# embedded-gw.net
KiCad netlist of a schematic drawn in EAGLE
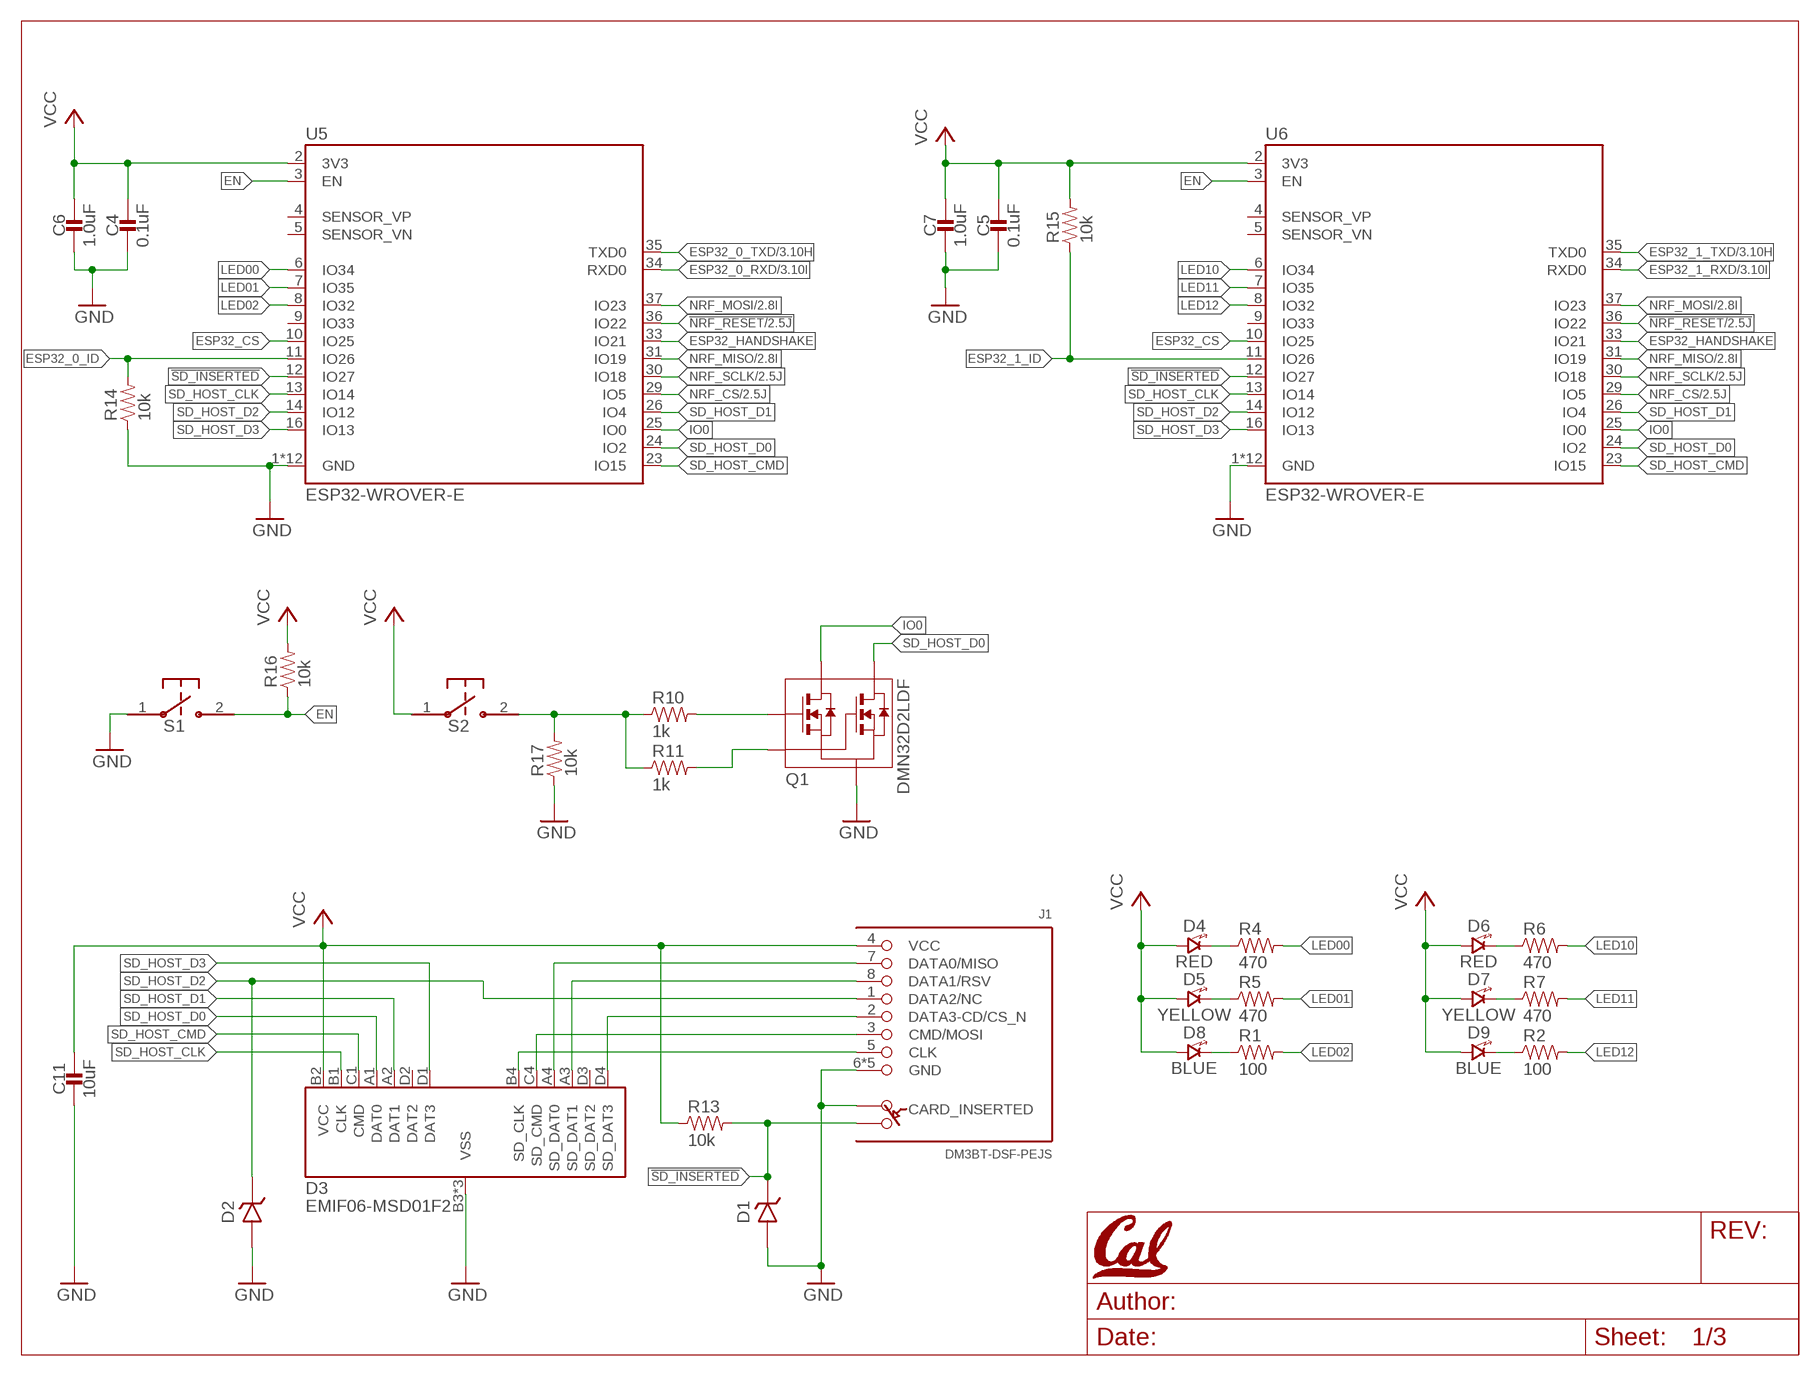
[diagram p0: schematic, sheet 1]
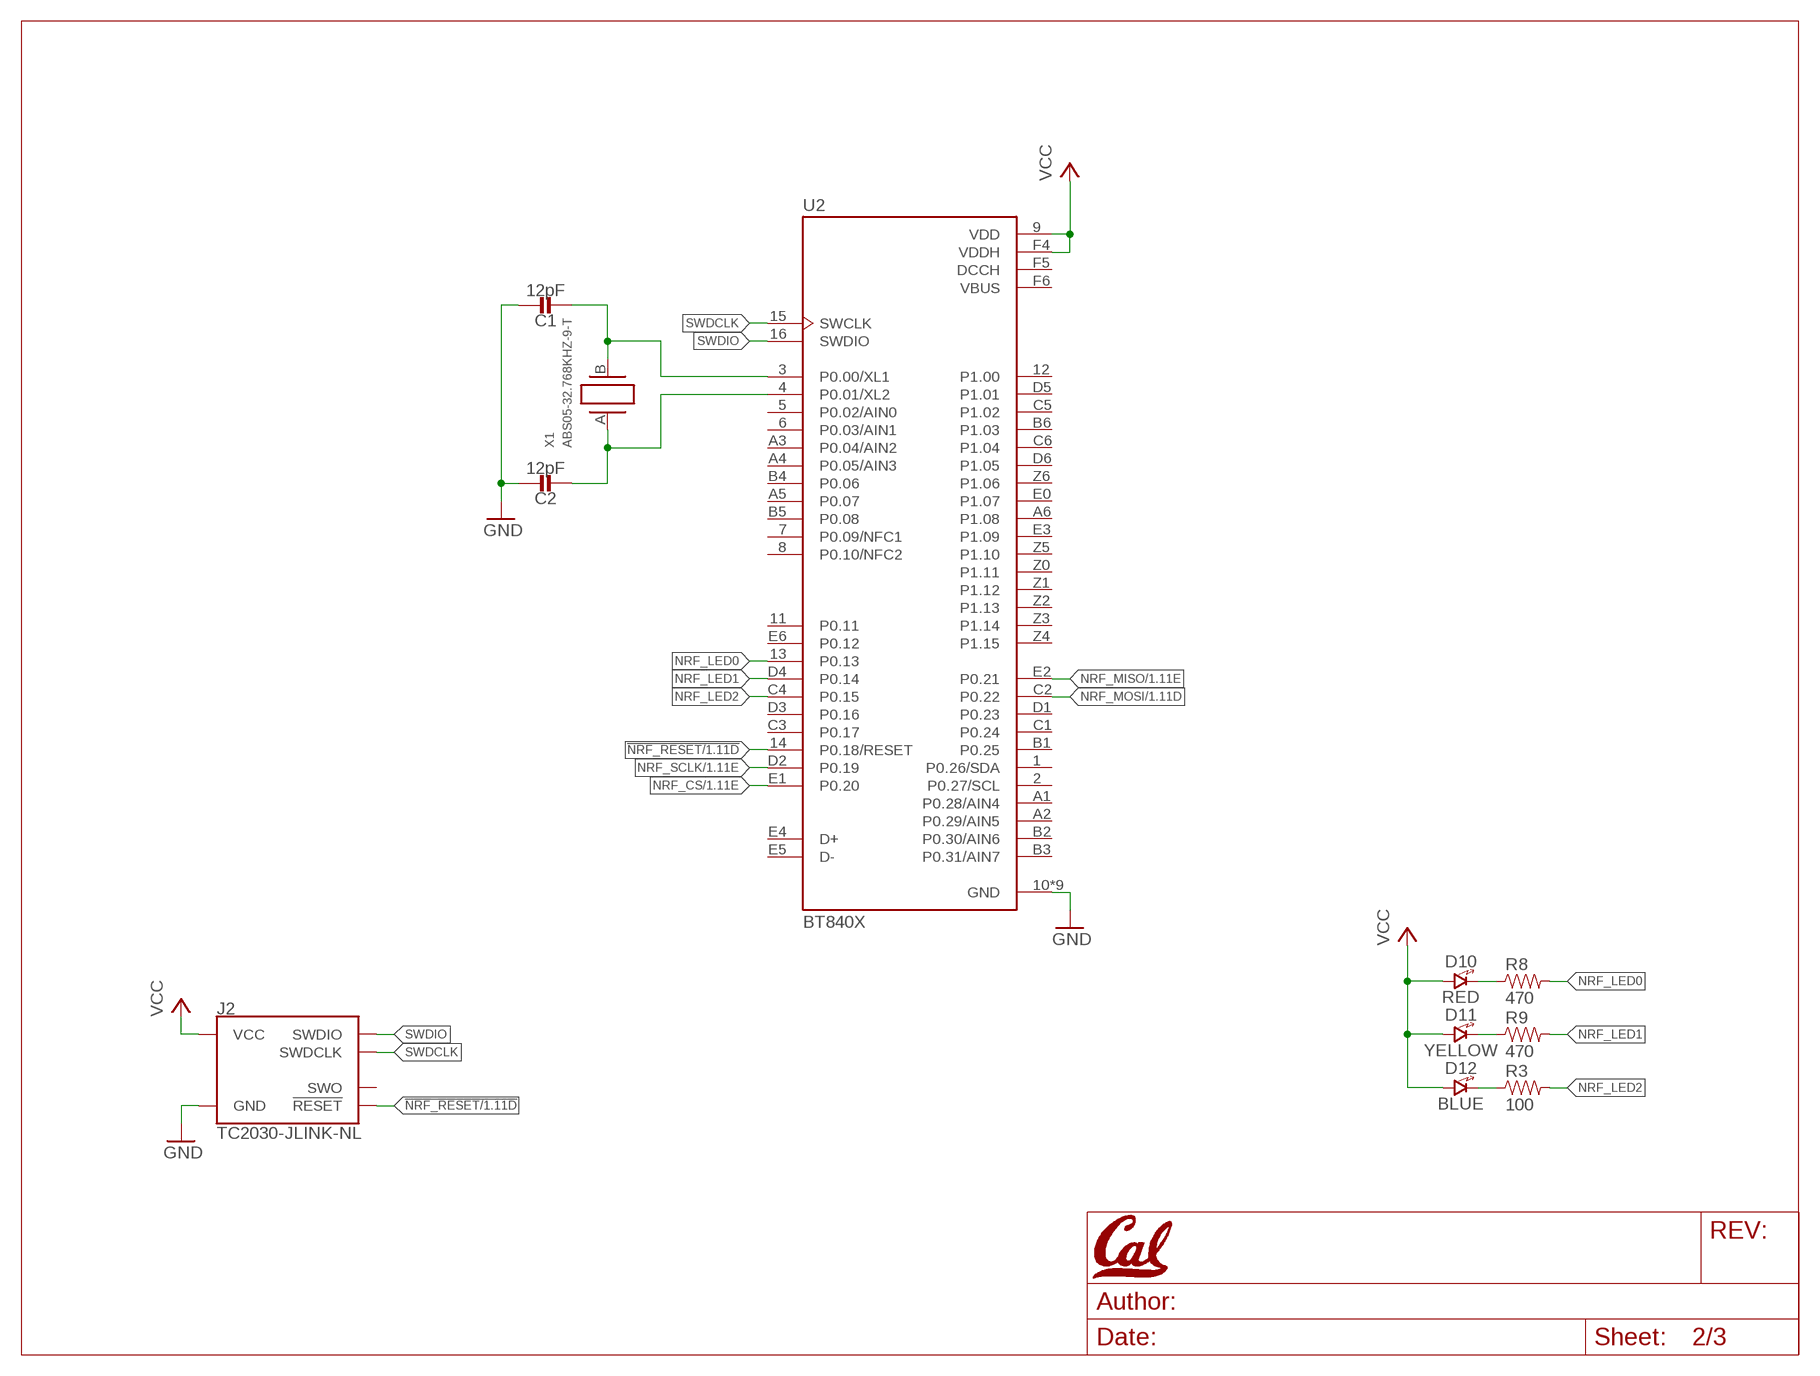
[diagram p1: schematic, sheet 2]
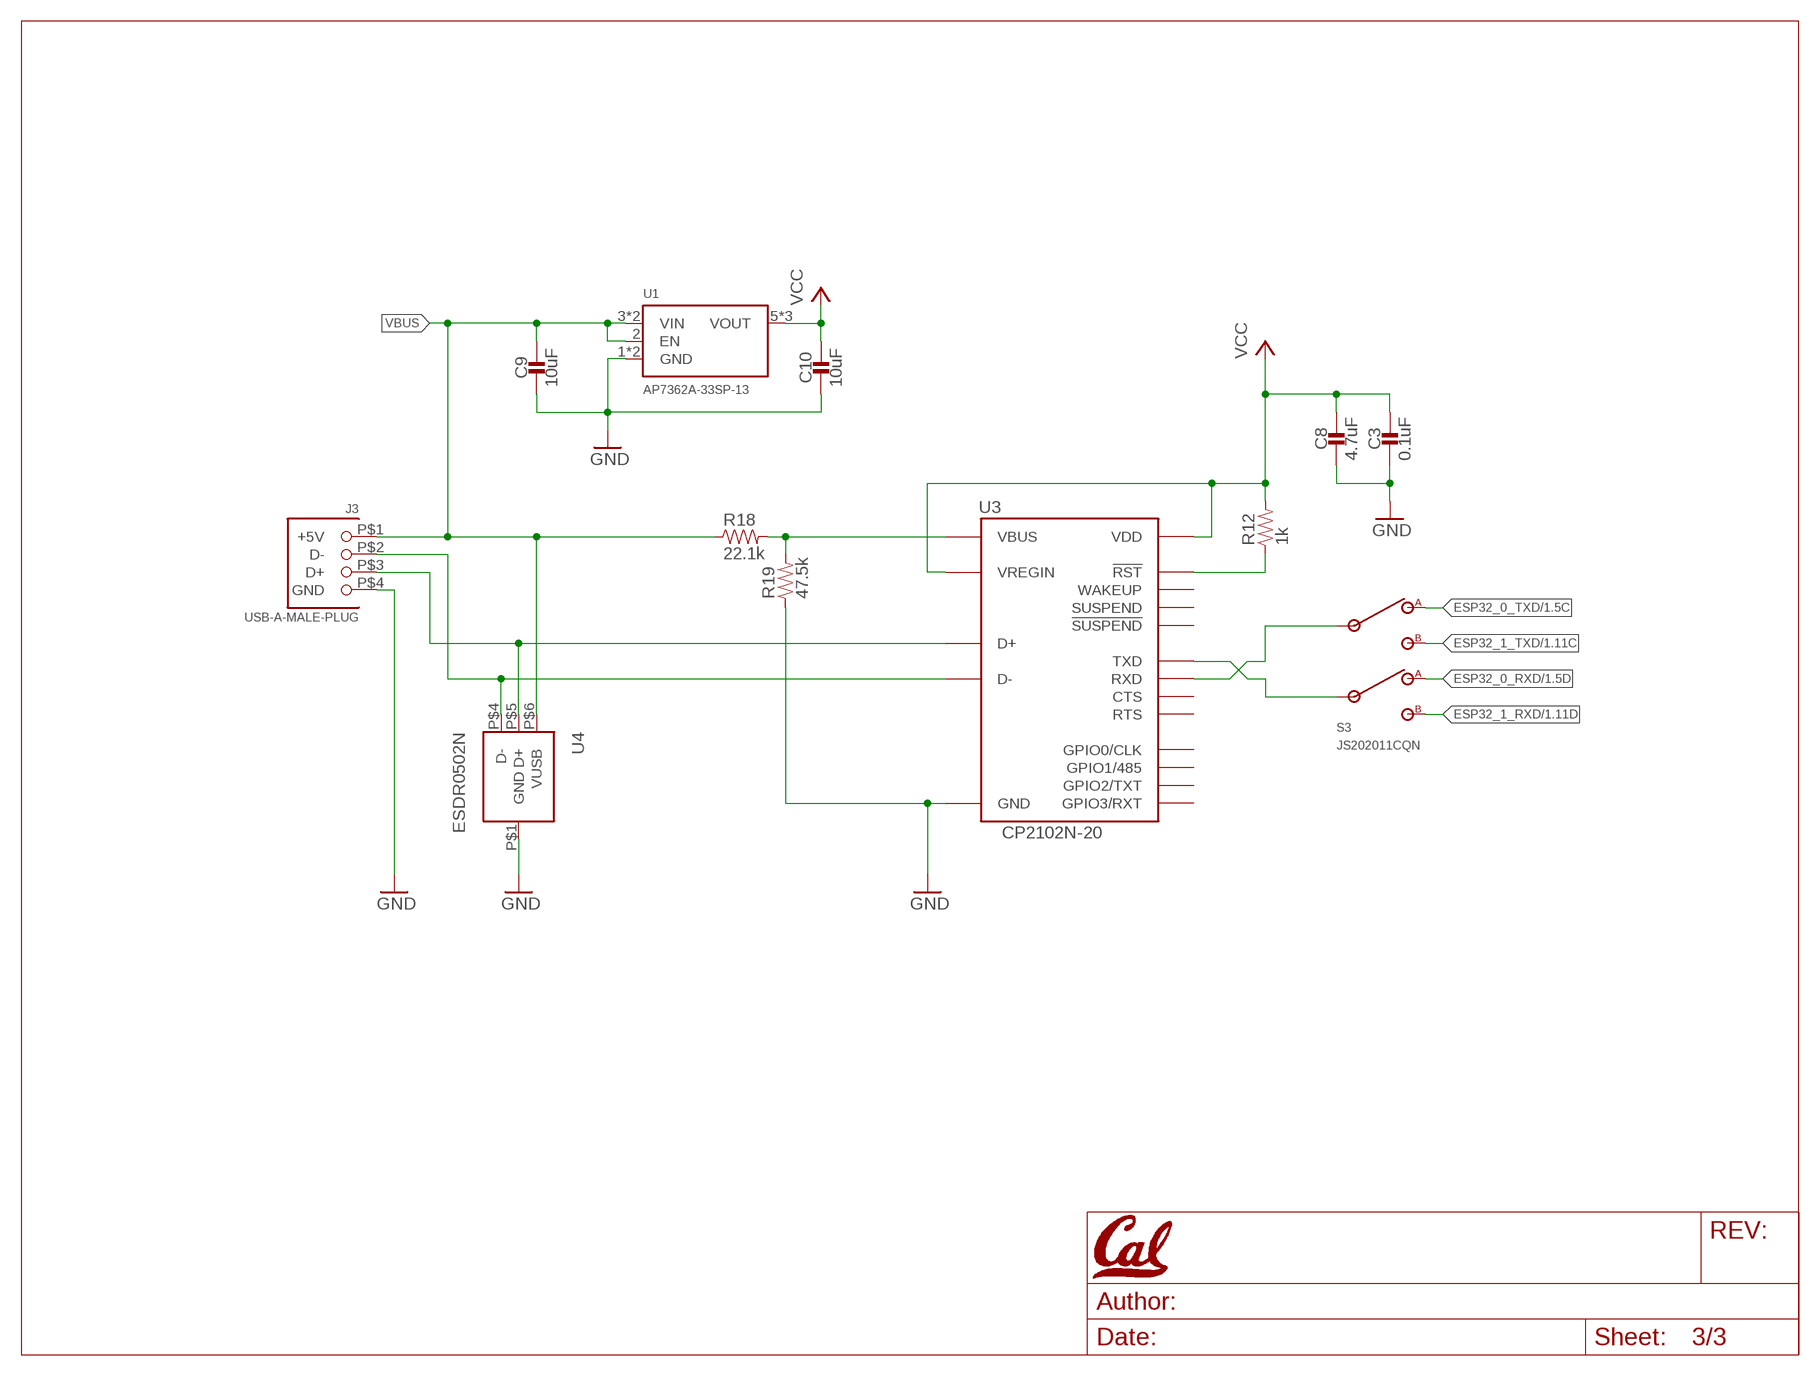
[diagram p2: schematic, sheet 3]

(export (version "E")
  (design (tool "Eeschema 10.0.6"))
  (components
    (comp (ref "C1")
      (value "12pF")
      (footprint "eagle-import:0402_CAP")
      (fields (field (name "MPN") "GCM1555C1H120GA16D"))
      (libsource (lib "eagle-import") (part "CAPACITOR0402_CAP"))
    )
    (comp (ref "C2")
      (value "12pF")
      (footprint "eagle-import:0402_CAP")
      (fields (field (name "MPN") "GCM1555C1H120GA16D"))
      (libsource (lib "eagle-import") (part "CAPACITOR0402_CAP"))
    )
    (comp (ref "D10")
      (value "RED")
      (footprint "eagle-import:LED-0603")
      (fields (field (name "MPN") "LTST-C193KRKT-5A"))
      (libsource (lib "eagle-import") (part "LED0603"))
    )
    (comp (ref "D11")
      (value "YELLOW")
      (footprint "eagle-import:LED-0603")
      (fields (field (name "MPN") "LTST-C193KSKT-5A"))
      (libsource (lib "eagle-import") (part "LED0603"))
    )
    (comp (ref "D12")
      (value "BLUE")
      (footprint "eagle-import:LED-0603")
      (fields (field (name "MPN") "LTST-C193TBKT-5A"))
      (libsource (lib "eagle-import") (part "LED0603"))
    )
    (comp (ref "J2")
      (value "TC2030-JLINK-NL")
      (footprint "eagle-import:TC2030-IDC-NL")
      (libsource (lib "eagle-import") (part "TC2030-JLINK-NL"))
    )
    (comp (ref "R3")
      (value "100")
      (footprint "eagle-import:0402_RES")
      (fields (field (name "MPN") "RC0402JR-07100RL"))
      (libsource (lib "eagle-import") (part "RESISTOR0402_RES"))
    )
    (comp (ref "R8")
      (value "470")
      (footprint "eagle-import:0402_RES")
      (fields (field (name "MPN") "RC0402FR-07470RL"))
      (libsource (lib "eagle-import") (part "RESISTOR0402_RES"))
    )
    (comp (ref "R9")
      (value "470")
      (footprint "eagle-import:0402_RES")
      (fields (field (name "MPN") "RC0402FR-07470RL"))
      (libsource (lib "eagle-import") (part "RESISTOR0402_RES"))
    )
    (comp (ref "U2")
      (value "BT840X")
      (footprint "eagle-import:XCVR_BT840X")
      (fields (field (name "MANUFACTURER") "Fanstel Corp."))
      (libsource (lib "eagle-import") (part "BT840X"))
    )
    (comp (ref "X1")
      (value "ABS05-32.768KHZ-9-T")
      (footprint "eagle-import:ABS05")
      (fields (field (name "MANUFACTURER") "Abracon"))
      (libsource (lib "eagle-import") (part "ABS05-32.768KHZ-9-T"))
    )
    (comp (ref "C4")
      (value "0.1uF")
      (footprint "eagle-import:0402_CAP")
      (fields (field (name "MPN") "CL05B104KQ5NNNC"))
      (libsource (lib "eagle-import") (part "CAPACITOR0402_CAP"))
    )
    (comp (ref "C5")
      (value "0.1uF")
      (footprint "eagle-import:0402_CAP")
      (fields (field (name "MPN") "CL05B104KQ5NNNC"))
      (libsource (lib "eagle-import") (part "CAPACITOR0402_CAP"))
    )
    (comp (ref "C6")
      (value "1.0uF")
      (footprint "eagle-import:0402_CAP")
      (fields (field (name "MPN") "CL05A105KQ5NNNC"))
      (libsource (lib "eagle-import") (part "CAPACITOR0402_CAP"))
    )
    (comp (ref "C7")
      (value "1.0uF")
      (footprint "eagle-import:0402_CAP")
      (fields (field (name "MPN") "CL05A105KQ5NNNC"))
      (libsource (lib "eagle-import") (part "CAPACITOR0402_CAP"))
    )
    (comp (ref "C11")
      (value "10uF")
      (footprint "eagle-import:0805_CAP")
      (fields (field (name "MPN") "CL21A106KQCLNNC"))
      (libsource (lib "eagle-import") (part "CAPACITOR0805_CAP"))
    )
    (comp (ref "D1")
      (value "DIODE_ZENER0201")
      (footprint "eagle-import:0201_DIODE")
      (fields (field (name "MPN") "ESD7381MUT5G"))
      (libsource (lib "eagle-import") (part "DIODE_ZENER0201"))
    )
    (comp (ref "D2")
      (value "DIODE_ZENER0201")
      (footprint "eagle-import:0201_DIODE")
      (fields (field (name "MPN") "ESD7381MUT5G"))
      (libsource (lib "eagle-import") (part "DIODE_ZENER0201"))
    )
    (comp (ref "D3")
      (value "EMIF06-MSD01F2")
      (footprint "eagle-import:BGA16C50P4X4_192X192X65N")
      (fields (field (name "MANUFACTURER") "STMicroelectronics"))
      (libsource (lib "eagle-import") (part "EMIF06-MSD01F2"))
    )
    (comp (ref "D4")
      (value "RED")
      (footprint "eagle-import:LED-0603")
      (fields (field (name "MPN") "LTST-C193KRKT-5A"))
      (libsource (lib "eagle-import") (part "LED0603"))
    )
    (comp (ref "D5")
      (value "YELLOW")
      (footprint "eagle-import:LED-0603")
      (fields (field (name "MPN") "LTST-C193KSKT-5A"))
      (libsource (lib "eagle-import") (part "LED0603"))
    )
    (comp (ref "D6")
      (value "RED")
      (footprint "eagle-import:LED-0603")
      (fields (field (name "MPN") "LTST-C193KRKT-5A"))
      (libsource (lib "eagle-import") (part "LED0603"))
    )
    (comp (ref "D7")
      (value "YELLOW")
      (footprint "eagle-import:LED-0603")
      (fields (field (name "MPN") "LTST-C193KSKT-5A"))
      (libsource (lib "eagle-import") (part "LED0603"))
    )
    (comp (ref "D8")
      (value "BLUE")
      (footprint "eagle-import:LED-0603")
      (fields (field (name "MPN") "LTST-C193TBKT-5A"))
      (libsource (lib "eagle-import") (part "LED0603"))
    )
    (comp (ref "D9")
      (value "BLUE")
      (footprint "eagle-import:LED-0603")
      (fields (field (name "MPN") "LTST-C193TBKT-5A"))
      (libsource (lib "eagle-import") (part "LED0603"))
    )
    (comp (ref "J1")
      (value "DM3BT-DSF-PEJS")
      (footprint "eagle-import:HRS_DM3BT-DSF-PEJS")
      (fields (field (name "MANUFACTURER") "Hirose Connector"))
      (libsource (lib "eagle-import") (part "DM3BT-DSF-PEJS"))
    )
    (comp (ref "Q1")
      (value "DMN32D2LDF")
      (footprint "eagle-import:SOT353")
      (fields (field (name "MANUFACTURER") "Diodes Incorporated") (field (name "MPN") "DMN32D2LDF-7"))
      (libsource (lib "eagle-import") (part "DMN32D2LDF"))
    )
    (comp (ref "R1")
      (value "100")
      (footprint "eagle-import:0402_RES")
      (fields (field (name "MPN") "RC0402JR-07100RL"))
      (libsource (lib "eagle-import") (part "RESISTOR0402_RES"))
    )
    (comp (ref "R2")
      (value "100")
      (footprint "eagle-import:0402_RES")
      (fields (field (name "MPN") "RC0402JR-07100RL"))
      (libsource (lib "eagle-import") (part "RESISTOR0402_RES"))
    )
    (comp (ref "R4")
      (value "470")
      (footprint "eagle-import:0402_RES")
      (fields (field (name "MPN") "RC0402FR-07470RL"))
      (libsource (lib "eagle-import") (part "RESISTOR0402_RES"))
    )
    (comp (ref "R5")
      (value "470")
      (footprint "eagle-import:0402_RES")
      (fields (field (name "MPN") "RC0402FR-07470RL"))
      (libsource (lib "eagle-import") (part "RESISTOR0402_RES"))
    )
    (comp (ref "R6")
      (value "470")
      (footprint "eagle-import:0402_RES")
      (fields (field (name "MPN") "RC0402FR-07470RL"))
      (libsource (lib "eagle-import") (part "RESISTOR0402_RES"))
    )
    (comp (ref "R7")
      (value "470")
      (footprint "eagle-import:0402_RES")
      (fields (field (name "MPN") "RC0402FR-07470RL"))
      (libsource (lib "eagle-import") (part "RESISTOR0402_RES"))
    )
    (comp (ref "R10")
      (value "1k")
      (footprint "eagle-import:0402_RES")
      (fields (field (name "MPN") "RMCF0402JT1K00"))
      (libsource (lib "eagle-import") (part "RESISTOR0402_RES"))
    )
    (comp (ref "R11")
      (value "1k")
      (footprint "eagle-import:0402_RES")
      (fields (field (name "MPN") "RMCF0402JT1K00"))
      (libsource (lib "eagle-import") (part "RESISTOR0402_RES"))
    )
    (comp (ref "R13")
      (value "10k")
      (footprint "eagle-import:0402_RES")
      (fields (field (name "MPN") "RMCF0402JT10K0"))
      (libsource (lib "eagle-import") (part "RESISTOR0402_RES"))
    )
    (comp (ref "R14")
      (value "10k")
      (footprint "eagle-import:0402_RES")
      (fields (field (name "MPN") "RMCF0402JT10K0"))
      (libsource (lib "eagle-import") (part "RESISTOR0402_RES"))
    )
    (comp (ref "R15")
      (value "10k")
      (footprint "eagle-import:0402_RES")
      (fields (field (name "MPN") "RMCF0402JT10K0"))
      (libsource (lib "eagle-import") (part "RESISTOR0402_RES"))
    )
    (comp (ref "R16")
      (value "10k")
      (footprint "eagle-import:0402_RES")
      (fields (field (name "MPN") "RMCF0402JT10K0"))
      (libsource (lib "eagle-import") (part "RESISTOR0402_RES"))
    )
    (comp (ref "R17")
      (value "10k")
      (footprint "eagle-import:0402_RES")
      (fields (field (name "MPN") "RMCF0402JT10K0"))
      (libsource (lib "eagle-import") (part "RESISTOR0402_RES"))
    )
    (comp (ref "S1")
      (value "B3U-1000P")
      (footprint "eagle-import:B3U-1000P")
      (fields (field (name "MANUFACTURER") "Omron"))
      (libsource (lib "eagle-import") (part "B3U-1000P"))
    )
    (comp (ref "S2")
      (value "B3U-1000P")
      (footprint "eagle-import:B3U-1000P")
      (fields (field (name "MANUFACTURER") "Omron"))
      (libsource (lib "eagle-import") (part "B3U-1000P"))
    )
    (comp (ref "U5")
      (value "ESP32-WROVER-E")
      (footprint "eagle-import:ESP32-WROVER-E")
      (fields (field (name "MANUFACTURER") "Espressif Systems") (field (name "MPN") "  ESP32-WROVER-E (8MB)"))
      (libsource (lib "eagle-import") (part "ESP32-WROVER-E"))
    )
    (comp (ref "U6")
      (value "ESP32-WROVER-E")
      (footprint "eagle-import:ESP32-WROVER-E")
      (fields (field (name "MANUFACTURER") "Espressif Systems") (field (name "MPN") "  ESP32-WROVER-E (8MB)"))
      (libsource (lib "eagle-import") (part "ESP32-WROVER-E"))
    )
    (comp (ref "C3")
      (value "0.1uF")
      (footprint "eagle-import:0402_CAP")
      (fields (field (name "MPN") "CL05B104KQ5NNNC"))
      (libsource (lib "eagle-import") (part "CAPACITOR0402_CAP"))
    )
    (comp (ref "C8")
      (value "4.7uF")
      (footprint "eagle-import:0603_CAP")
      (fields (field (name "MPN") "CL10A475KQ8NNNC"))
      (libsource (lib "eagle-import") (part "CAPACITOR0603_CAP"))
    )
    (comp (ref "C9")
      (value "10uF")
      (footprint "eagle-import:0805_CAP")
      (fields (field (name "MPN") "CL21A106KQCLNNC"))
      (libsource (lib "eagle-import") (part "CAPACITOR0805_CAP"))
    )
    (comp (ref "C10")
      (value "10uF")
      (footprint "eagle-import:0805_CAP")
      (fields (field (name "MPN") "CL21A106KQCLNNC"))
      (libsource (lib "eagle-import") (part "CAPACITOR0805_CAP"))
    )
    (comp (ref "J3")
      (value "USB-A-MALE-PLUG")
      (footprint "eagle-import:USB_A_MALE_PLUG_CUI_UP2-AH")
      (fields (field (name "MANUFACTURER") "CUI") (field (name "MPN") "UP2-AH-1-TH"))
      (libsource (lib "eagle-import") (part "USB-A-MALE-PLUG"))
    )
    (comp (ref "R12")
      (value "1k")
      (footprint "eagle-import:0402_RES")
      (fields (field (name "MPN") "RMCF0402JT1K00"))
      (libsource (lib "eagle-import") (part "RESISTOR0402_RES"))
    )
    (comp (ref "R18")
      (value "22.1k")
      (footprint "eagle-import:0402_RES")
      (fields (field (name "MPN") "RC0402FR-0722K1L"))
      (libsource (lib "eagle-import") (part "RESISTOR0402_RES"))
    )
    (comp (ref "R19")
      (value "47.5k")
      (footprint "eagle-import:0402_RES")
      (fields (field (name "MPN") "RT0402FRE0722K1L"))
      (libsource (lib "eagle-import") (part "RESISTOR0402_RES"))
    )
    (comp (ref "S3")
      (value "JS202011CQN")
      (footprint "eagle-import:JS202011CQN")
      (fields (field (name "MANUFACTURER") "C&K"))
      (libsource (lib "eagle-import") (part "JS202011CQN"))
    )
    (comp (ref "U1")
      (value "AP7362A-33SP-13")
      (footprint "eagle-import:SO-8EP")
      (fields (field (name "MANUFACTURER") "Diodes Incorporated") (field (name "MPN") "AP7362A-33SP-13 "))
      (libsource (lib "eagle-import") (part "AP7362A-33SP-13"))
    )
    (comp (ref "U3")
      (value "CP2102N-20")
      (footprint "eagle-import:QFN-20-3MM")
      (fields (field (name "MANUFACTURER") "SiLabs") (field (name "MPN") "CP2102N-A01-GQFN20"))
      (libsource (lib "eagle-import") (part "CP2102N-20"))
    )
    (comp (ref "U4")
      (value "ESDR0502N")
      (footprint "eagle-import:UDFN-6")
      (fields (field (name "MPN") "ESDR0502NMUTBG"))
      (libsource (lib "eagle-import") (part "ESDR0502N"))
    )
  )
  (nets
    (net (code "1") (name "DCCH") (class "Default")
      (node (ref "U2") (pin "F5") (pinfunction "DCCH_F5") (pintype "power_in"))
    )
    (net (code "2") (name "EN") (class "Default")
      (node (ref "R16") (pin "1") (pinfunction "1_1") (pintype "passive"))
      (node (ref "S1") (pin "2") (pinfunction "P$2_2") (pintype "passive"))
      (node (ref "U5") (pin "3") (pinfunction "EN_3") (pintype "bidirectional"))
      (node (ref "U6") (pin "3") (pinfunction "EN_3") (pintype "bidirectional"))
    )
    (net (code "3") (name "ESP32_0_ID") (class "Default")
      (node (ref "R14") (pin "2") (pinfunction "2_2") (pintype "passive"))
      (node (ref "U5") (pin "11") (pinfunction "IO26_11") (pintype "bidirectional"))
    )
    (net (code "4") (name "ESP32_0_RXD") (class "Default")
      (node (ref "S3") (pin "1") (pinfunction "A2_1") (pintype "bidirectional"))
      (node (ref "U5") (pin "34") (pinfunction "RXD0_34") (pintype "bidirectional"))
    )
    (net (code "5") (name "ESP32_0_TXD") (class "Default")
      (node (ref "S3") (pin "4") (pinfunction "A1_4") (pintype "bidirectional"))
      (node (ref "U5") (pin "35") (pinfunction "TXD0_35") (pintype "bidirectional"))
    )
    (net (code "6") (name "ESP32_1_ID") (class "Default")
      (node (ref "R15") (pin "1") (pinfunction "1_1") (pintype "passive"))
      (node (ref "U6") (pin "11") (pinfunction "IO26_11") (pintype "bidirectional"))
    )
    (net (code "7") (name "ESP32_1_RXD") (class "Default")
      (node (ref "S3") (pin "3") (pinfunction "B2_3") (pintype "bidirectional"))
      (node (ref "U6") (pin "34") (pinfunction "RXD0_34") (pintype "bidirectional"))
    )
    (net (code "8") (name "ESP32_1_TXD") (class "Default")
      (node (ref "S3") (pin "6") (pinfunction "B1_6") (pintype "bidirectional"))
      (node (ref "U6") (pin "35") (pinfunction "TXD0_35") (pintype "bidirectional"))
    )
    (net (code "9") (name "ESP32_CS") (class "Default")
      (node (ref "U5") (pin "10") (pinfunction "IO25_10") (pintype "bidirectional"))
      (node (ref "U6") (pin "10") (pinfunction "IO25_10") (pintype "bidirectional"))
    )
    (net (code "10") (name "ESP32_HANDSHAKE") (class "Default")
      (node (ref "U5") (pin "33") (pinfunction "IO21_33") (pintype "bidirectional"))
      (node (ref "U6") (pin "33") (pinfunction "IO21_33") (pintype "bidirectional"))
    )
    (net (code "11") (name "GND") (class "Default")
      (node (ref "C1") (pin "1") (pinfunction "1_1") (pintype "bidirectional"))
      (node (ref "C10") (pin "P$2") (pinfunction "2_P$2") (pintype "bidirectional"))
      (node (ref "C11") (pin "P$2") (pinfunction "2_P$2") (pintype "bidirectional"))
      (node (ref "C2") (pin "1") (pinfunction "1_1") (pintype "bidirectional"))
      (node (ref "C3") (pin "2") (pinfunction "2_2") (pintype "bidirectional"))
      (node (ref "C4") (pin "2") (pinfunction "2_2") (pintype "bidirectional"))
      (node (ref "C5") (pin "2") (pinfunction "2_2") (pintype "bidirectional"))
      (node (ref "C6") (pin "2") (pinfunction "2_2") (pintype "bidirectional"))
      (node (ref "C7") (pin "2") (pinfunction "2_2") (pintype "bidirectional"))
      (node (ref "C8") (pin "2") (pinfunction "2_2") (pintype "bidirectional"))
      (node (ref "C9") (pin "P$2") (pinfunction "2_P$2") (pintype "bidirectional"))
      (node (ref "D1") (pin "P$2") (pinfunction "ANODE_P$2") (pintype "bidirectional"))
      (node (ref "D2") (pin "P$2") (pinfunction "ANODE_P$2") (pintype "bidirectional"))
      (node (ref "D3") (pin "B3") (pinfunction "VSS_B3") (pintype "bidirectional"))
      (node (ref "D3") (pin "C2") (pinfunction "VSS_C2") (pintype "bidirectional"))
      (node (ref "D3") (pin "C3") (pinfunction "VSS_C3") (pintype "bidirectional"))
      (node (ref "J1") (pin "6") (pinfunction "GND_6") (pintype "bidirectional"))
      (node (ref "J1") (pin "S1") (pinfunction "GND_S1") (pintype "bidirectional"))
      (node (ref "J1") (pin "S2") (pinfunction "GND_S2") (pintype "bidirectional"))
      (node (ref "J1") (pin "S3") (pinfunction "GND_S3") (pintype "bidirectional"))
      (node (ref "J1") (pin "S4") (pinfunction "GND_S4") (pintype "bidirectional"))
      (node (ref "J1") (pin "SW-A") (pinfunction "A_SW-A") (pintype "bidirectional"))
      (node (ref "J2") (pin "5") (pinfunction "GND_5") (pintype "bidirectional"))
      (node (ref "J3") (pin "P$4") (pinfunction "GND_P$4") (pintype "bidirectional"))
      (node (ref "Q1") (pin "S") (pinfunction "S_S") (pintype "bidirectional"))
      (node (ref "R14") (pin "1") (pinfunction "1_1") (pintype "passive"))
      (node (ref "R17") (pin "1") (pinfunction "1_1") (pintype "passive"))
      (node (ref "R19") (pin "1") (pinfunction "1_1") (pintype "passive"))
      (node (ref "S1") (pin "1") (pinfunction "P$1_1") (pintype "passive"))
      (node (ref "U1") (pin "1") (pinfunction "GND_1") (pintype "bidirectional"))
      (node (ref "U1") (pin "PAD") (pinfunction "GND_PAD") (pintype "bidirectional"))
      (node (ref "U2") (pin "10") (pinfunction "GND_10") (pintype "power_in"))
      (node (ref "U2") (pin "A0") (pinfunction "GND_A0") (pintype "power_in"))
      (node (ref "U2") (pin "B0") (pinfunction "GND_B0") (pintype "power_in"))
      (node (ref "U2") (pin "C0") (pinfunction "GND_C0") (pintype "power_in"))
      (node (ref "U2") (pin "D0") (pinfunction "GND_D0") (pintype "power_in"))
      (node (ref "U2") (pin "F0") (pinfunction "GND_F0") (pintype "power_in"))
      (node (ref "U2") (pin "F1") (pinfunction "GND_F1") (pintype "power_in"))
      (node (ref "U2") (pin "F2") (pinfunction "GND_F2") (pintype "power_in"))
      (node (ref "U2") (pin "F3") (pinfunction "GND_F3") (pintype "power_in"))
      (node (ref "U3") (pin "12") (pinfunction "GND_12") (pintype "bidirectional"))
      (node (ref "U3") (pin "3") (pinfunction "GND_3") (pintype "bidirectional"))
      (node (ref "U3") (pin "P$1") (pinfunction "GND_P$1") (pintype "bidirectional"))
      (node (ref "U4") (pin "P$1") (pinfunction "GND_P$1") (pintype "bidirectional"))
      (node (ref "U5") (pin "1") (pinfunction "GND_1") (pintype "bidirectional"))
      (node (ref "U5") (pin "15") (pinfunction "GND_15") (pintype "bidirectional"))
      (node (ref "U5") (pin "38") (pinfunction "GND_38") (pintype "bidirectional"))
      (node (ref "U5") (pin "GND1") (pinfunction "GND_GND1") (pintype "bidirectional"))
      (node (ref "U5") (pin "GND2") (pinfunction "GND_GND2") (pintype "bidirectional"))
      (node (ref "U5") (pin "GND3") (pinfunction "GND_GND3") (pintype "bidirectional"))
      (node (ref "U5") (pin "GND4") (pinfunction "GND_GND4") (pintype "bidirectional"))
      (node (ref "U5") (pin "GND5") (pinfunction "GND_GND5") (pintype "bidirectional"))
      (node (ref "U5") (pin "GND6") (pinfunction "GND_GND6") (pintype "bidirectional"))
      (node (ref "U5") (pin "GND7") (pinfunction "GND_GND7") (pintype "bidirectional"))
      (node (ref "U5") (pin "GND8") (pinfunction "GND_GND8") (pintype "bidirectional"))
      (node (ref "U5") (pin "GND9") (pinfunction "GND_GND9") (pintype "bidirectional"))
      (node (ref "U6") (pin "1") (pinfunction "GND_1") (pintype "bidirectional"))
      (node (ref "U6") (pin "15") (pinfunction "GND_15") (pintype "bidirectional"))
      (node (ref "U6") (pin "38") (pinfunction "GND_38") (pintype "bidirectional"))
      (node (ref "U6") (pin "GND1") (pinfunction "GND_GND1") (pintype "bidirectional"))
      (node (ref "U6") (pin "GND2") (pinfunction "GND_GND2") (pintype "bidirectional"))
      (node (ref "U6") (pin "GND3") (pinfunction "GND_GND3") (pintype "bidirectional"))
      (node (ref "U6") (pin "GND4") (pinfunction "GND_GND4") (pintype "bidirectional"))
      (node (ref "U6") (pin "GND5") (pinfunction "GND_GND5") (pintype "bidirectional"))
      (node (ref "U6") (pin "GND6") (pinfunction "GND_GND6") (pintype "bidirectional"))
      (node (ref "U6") (pin "GND7") (pinfunction "GND_GND7") (pintype "bidirectional"))
      (node (ref "U6") (pin "GND8") (pinfunction "GND_GND8") (pintype "bidirectional"))
      (node (ref "U6") (pin "GND9") (pinfunction "GND_GND9") (pintype "bidirectional"))
    )
    (net (code "12") (name "IO0") (class "Default")
      (node (ref "Q1") (pin "D1") (pinfunction "D1_D1") (pintype "bidirectional"))
      (node (ref "U5") (pin "25") (pinfunction "IO0_25") (pintype "bidirectional"))
      (node (ref "U6") (pin "25") (pinfunction "IO0_25") (pintype "bidirectional"))
    )
    (net (code "13") (name "LED00") (class "Default")
      (node (ref "R4") (pin "2") (pinfunction "2_2") (pintype "passive"))
      (node (ref "U5") (pin "6") (pinfunction "IO34_6") (pintype "bidirectional"))
    )
    (net (code "14") (name "LED01") (class "Default")
      (node (ref "R5") (pin "2") (pinfunction "2_2") (pintype "passive"))
      (node (ref "U5") (pin "7") (pinfunction "IO35_7") (pintype "bidirectional"))
    )
    (net (code "15") (name "LED02") (class "Default")
      (node (ref "R1") (pin "2") (pinfunction "2_2") (pintype "passive"))
      (node (ref "U5") (pin "8") (pinfunction "IO32_8") (pintype "bidirectional"))
    )
    (net (code "16") (name "LED10") (class "Default")
      (node (ref "R6") (pin "2") (pinfunction "2_2") (pintype "passive"))
      (node (ref "U6") (pin "6") (pinfunction "IO34_6") (pintype "bidirectional"))
    )
    (net (code "17") (name "LED11") (class "Default")
      (node (ref "R7") (pin "2") (pinfunction "2_2") (pintype "passive"))
      (node (ref "U6") (pin "7") (pinfunction "IO35_7") (pintype "bidirectional"))
    )
    (net (code "18") (name "LED12") (class "Default")
      (node (ref "R2") (pin "2") (pinfunction "2_2") (pintype "passive"))
      (node (ref "U6") (pin "8") (pinfunction "IO32_8") (pintype "bidirectional"))
    )
    (net (code "19") (name "NRF_CS") (class "Default")
      (node (ref "U2") (pin "E1") (pinfunction "P0.20_E1") (pintype "bidirectional"))
      (node (ref "U5") (pin "29") (pinfunction "IO5_29") (pintype "bidirectional"))
      (node (ref "U6") (pin "29") (pinfunction "IO5_29") (pintype "bidirectional"))
    )
    (net (code "20") (name "NRF_LED0") (class "Default")
      (node (ref "R8") (pin "2") (pinfunction "2_2") (pintype "passive"))
      (node (ref "U2") (pin "13") (pinfunction "P0.13_13") (pintype "bidirectional"))
    )
    (net (code "21") (name "NRF_LED1") (class "Default")
      (node (ref "R9") (pin "2") (pinfunction "2_2") (pintype "passive"))
      (node (ref "U2") (pin "D4") (pinfunction "P0.14_D4") (pintype "bidirectional"))
    )
    (net (code "22") (name "NRF_LED2") (class "Default")
      (node (ref "R3") (pin "2") (pinfunction "2_2") (pintype "passive"))
      (node (ref "U2") (pin "C4") (pinfunction "P0.15_C4") (pintype "bidirectional"))
    )
    (net (code "23") (name "NRF_MISO") (class "Default")
      (node (ref "U2") (pin "E2") (pinfunction "P0.21_E2") (pintype "bidirectional"))
      (node (ref "U5") (pin "31") (pinfunction "IO19_31") (pintype "bidirectional"))
      (node (ref "U6") (pin "31") (pinfunction "IO19_31") (pintype "bidirectional"))
    )
    (net (code "24") (name "NRF_MOSI") (class "Default")
      (node (ref "U2") (pin "C2") (pinfunction "P0.22_C2") (pintype "bidirectional"))
      (node (ref "U5") (pin "37") (pinfunction "IO23_37") (pintype "bidirectional"))
      (node (ref "U6") (pin "37") (pinfunction "IO23_37") (pintype "bidirectional"))
    )
    (net (code "25") (name "NRF_SCLK") (class "Default")
      (node (ref "U2") (pin "D2") (pinfunction "P0.19_D2") (pintype "bidirectional"))
      (node (ref "U5") (pin "30") (pinfunction "IO18_30") (pintype "bidirectional"))
      (node (ref "U6") (pin "30") (pinfunction "IO18_30") (pintype "bidirectional"))
    )
    (net (code "26") (name "Net-(D3-SD_CLK)") (class "Default")
      (node (ref "D3") (pin "B4") (pinfunction "SD_CLK_B4") (pintype "bidirectional"))
      (node (ref "J1") (pin "5") (pinfunction "CLK_5") (pintype "bidirectional"))
    )
    (net (code "27") (name "Net-(D3-SD_CMD)") (class "Default")
      (node (ref "D3") (pin "C4") (pinfunction "SD_CMD_C4") (pintype "bidirectional"))
      (node (ref "J1") (pin "3") (pinfunction "CMD/MOSI_3") (pintype "bidirectional"))
    )
    (net (code "28") (name "Net-(D3-SD_DAT0)") (class "Default")
      (node (ref "D3") (pin "A4") (pinfunction "SD_DAT0_A4") (pintype "bidirectional"))
      (node (ref "J1") (pin "7") (pinfunction "DATA0/MISO_7") (pintype "bidirectional"))
    )
    (net (code "29") (name "Net-(D3-SD_DAT1)") (class "Default")
      (node (ref "D3") (pin "A3") (pinfunction "SD_DAT1_A3") (pintype "bidirectional"))
      (node (ref "J1") (pin "8") (pinfunction "DATA1/RSV_8") (pintype "bidirectional"))
    )
    (net (code "30") (name "Net-(D3-SD_DAT3)") (class "Default")
      (node (ref "D3") (pin "D4") (pinfunction "SD_DAT3_D4") (pintype "bidirectional"))
      (node (ref "J1") (pin "2") (pinfunction "DATA3-CD/CS_N_2") (pintype "bidirectional"))
    )
    (net (code "31") (name "Net-(D4-CATHODE)") (class "Default")
      (node (ref "D4") (pin "C") (pinfunction "CATHODE_C") (pintype "bidirectional"))
      (node (ref "R4") (pin "1") (pinfunction "1_1") (pintype "passive"))
    )
    (net (code "32") (name "Net-(D5-CATHODE)") (class "Default")
      (node (ref "D5") (pin "C") (pinfunction "CATHODE_C") (pintype "bidirectional"))
      (node (ref "R5") (pin "1") (pinfunction "1_1") (pintype "passive"))
    )
    (net (code "33") (name "Net-(D6-CATHODE)") (class "Default")
      (node (ref "D6") (pin "C") (pinfunction "CATHODE_C") (pintype "bidirectional"))
      (node (ref "R6") (pin "1") (pinfunction "1_1") (pintype "passive"))
    )
    (net (code "34") (name "Net-(D7-CATHODE)") (class "Default")
      (node (ref "D7") (pin "C") (pinfunction "CATHODE_C") (pintype "bidirectional"))
      (node (ref "R7") (pin "1") (pinfunction "1_1") (pintype "passive"))
    )
    (net (code "35") (name "Net-(D8-CATHODE)") (class "Default")
      (node (ref "D8") (pin "C") (pinfunction "CATHODE_C") (pintype "bidirectional"))
      (node (ref "R1") (pin "1") (pinfunction "1_1") (pintype "passive"))
    )
    (net (code "36") (name "Net-(D9-CATHODE)") (class "Default")
      (node (ref "D9") (pin "C") (pinfunction "CATHODE_C") (pintype "bidirectional"))
      (node (ref "R2") (pin "1") (pinfunction "1_1") (pintype "passive"))
    )
    (net (code "37") (name "Net-(D10-CATHODE)") (class "Default")
      (node (ref "D10") (pin "C") (pinfunction "CATHODE_C") (pintype "bidirectional"))
      (node (ref "R8") (pin "1") (pinfunction "1_1") (pintype "passive"))
    )
    (net (code "38") (name "Net-(D11-CATHODE)") (class "Default")
      (node (ref "D11") (pin "C") (pinfunction "CATHODE_C") (pintype "bidirectional"))
      (node (ref "R9") (pin "1") (pinfunction "1_1") (pintype "passive"))
    )
    (net (code "39") (name "Net-(D12-CATHODE)") (class "Default")
      (node (ref "D12") (pin "C") (pinfunction "CATHODE_C") (pintype "bidirectional"))
      (node (ref "R3") (pin "1") (pinfunction "1_1") (pintype "passive"))
    )
    (net (code "40") (name "Net-(J3-D+)") (class "Default")
      (node (ref "J3") (pin "P$3") (pinfunction "D+_P$3") (pintype "bidirectional"))
      (node (ref "U3") (pin "4") (pinfunction "D+_4") (pintype "bidirectional"))
      (node (ref "U4") (pin "P$5") (pinfunction "D+_P$5") (pintype "bidirectional"))
    )
    (net (code "41") (name "Net-(J3-D-)") (class "Default")
      (node (ref "J3") (pin "P$2") (pinfunction "D-_P$2") (pintype "bidirectional"))
      (node (ref "U3") (pin "5") (pinfunction "D-_5") (pintype "bidirectional"))
      (node (ref "U4") (pin "P$4") (pinfunction "D-_P$4") (pintype "bidirectional"))
    )
    (net (code "42") (name "Net-(Q1-PadG1)") (class "Default")
      (node (ref "Q1") (pin "G1") (pinfunction "G1_G1") (pintype "input"))
      (node (ref "R10") (pin "2") (pinfunction "2_2") (pintype "passive"))
    )
    (net (code "43") (name "Net-(Q1-PadG2)") (class "Default")
      (node (ref "Q1") (pin "G2") (pinfunction "G2_G2") (pintype "input"))
      (node (ref "R11") (pin "2") (pinfunction "2_2") (pintype "passive"))
    )
    (net (code "44") (name "Net-(S2-P$2)") (class "Default")
      (node (ref "R10") (pin "1") (pinfunction "1_1") (pintype "passive"))
      (node (ref "R11") (pin "1") (pinfunction "1_1") (pintype "passive"))
      (node (ref "R17") (pin "2") (pinfunction "2_2") (pintype "passive"))
      (node (ref "S2") (pin "2") (pinfunction "P$2_2") (pintype "passive"))
    )
    (net (code "45") (name "Net-(S3-I1)") (class "Default")
      (node (ref "S3") (pin "5") (pinfunction "I1_5") (pintype "bidirectional"))
      (node (ref "U3") (pin "17") (pinfunction "RXD_17") (pintype "bidirectional"))
    )
    (net (code "46") (name "Net-(S3-I2)") (class "Default")
      (node (ref "S3") (pin "2") (pinfunction "I2_2") (pintype "bidirectional"))
      (node (ref "U3") (pin "18") (pinfunction "TXD_18") (pintype "bidirectional"))
    )
    (net (code "47") (name "Net-(U2-P0.00{slash}XL1)") (class "Default")
      (node (ref "C1") (pin "2") (pinfunction "2_2") (pintype "bidirectional"))
      (node (ref "U2") (pin "3") (pinfunction "P0.00/XL1_3") (pintype "bidirectional"))
      (node (ref "X1") (pin "B") (pinfunction "2_B") (pintype "bidirectional"))
    )
    (net (code "48") (name "Net-(U2-P0.01{slash}XL2)") (class "Default")
      (node (ref "C2") (pin "2") (pinfunction "2_2") (pintype "bidirectional"))
      (node (ref "U2") (pin "4") (pinfunction "P0.01/XL2_4") (pintype "bidirectional"))
      (node (ref "X1") (pin "A") (pinfunction "1_A") (pintype "bidirectional"))
    )
    (net (code "49") (name "Net-(U3-VBUS)") (class "Default")
      (node (ref "R18") (pin "2") (pinfunction "2_2") (pintype "passive"))
      (node (ref "R19") (pin "2") (pinfunction "2_2") (pintype "passive"))
      (node (ref "U3") (pin "8") (pinfunction "VBUS_8") (pintype "bidirectional"))
    )
    (net (code "50") (name "Net-(U3-~{RST})") (class "Default")
      (node (ref "R12") (pin "1") (pinfunction "1_1") (pintype "passive"))
      (node (ref "U3") (pin "9") (pinfunction "~{RST}_9") (pintype "bidirectional"))
    )
    (net (code "51") (name "SD_HOST_CLK") (class "Default")
      (node (ref "D3") (pin "B1") (pinfunction "CLK_B1") (pintype "bidirectional"))
      (node (ref "U5") (pin "13") (pinfunction "IO14_13") (pintype "bidirectional"))
      (node (ref "U6") (pin "13") (pinfunction "IO14_13") (pintype "bidirectional"))
    )
    (net (code "52") (name "SD_HOST_CMD") (class "Default")
      (node (ref "D3") (pin "C1") (pinfunction "CMD_C1") (pintype "bidirectional"))
      (node (ref "U5") (pin "23") (pinfunction "IO15_23") (pintype "bidirectional"))
      (node (ref "U6") (pin "23") (pinfunction "IO15_23") (pintype "bidirectional"))
    )
    (net (code "53") (name "SD_HOST_D0") (class "Default")
      (node (ref "D3") (pin "A1") (pinfunction "DAT0_A1") (pintype "bidirectional"))
      (node (ref "Q1") (pin "D2") (pinfunction "D2_D2") (pintype "bidirectional"))
      (node (ref "U5") (pin "24") (pinfunction "IO2_24") (pintype "bidirectional"))
      (node (ref "U6") (pin "24") (pinfunction "IO2_24") (pintype "bidirectional"))
    )
    (net (code "54") (name "SD_HOST_D1") (class "Default")
      (node (ref "D3") (pin "A2") (pinfunction "DAT1_A2") (pintype "bidirectional"))
      (node (ref "U5") (pin "26") (pinfunction "IO4_26") (pintype "bidirectional"))
      (node (ref "U6") (pin "26") (pinfunction "IO4_26") (pintype "bidirectional"))
    )
    (net (code "55") (name "SD_HOST_D2") (class "Default")
      (node (ref "D2") (pin "P$1") (pinfunction "CATHODE_P$1") (pintype "bidirectional"))
      (node (ref "J1") (pin "1") (pinfunction "DATA2/NC_1") (pintype "bidirectional"))
      (node (ref "U5") (pin "14") (pinfunction "IO12_14") (pintype "bidirectional"))
      (node (ref "U6") (pin "14") (pinfunction "IO12_14") (pintype "bidirectional"))
    )
    (net (code "56") (name "SD_HOST_D3") (class "Default")
      (node (ref "D3") (pin "D1") (pinfunction "DAT3_D1") (pintype "bidirectional"))
      (node (ref "U5") (pin "16") (pinfunction "IO13_16") (pintype "bidirectional"))
      (node (ref "U6") (pin "16") (pinfunction "IO13_16") (pintype "bidirectional"))
    )
    (net (code "57") (name "SWDCLK") (class "Default")
      (node (ref "J2") (pin "4") (pinfunction "SWDCLK_4") (pintype "bidirectional"))
      (node (ref "U2") (pin "15") (pinfunction "SWCLK_15") (pintype "input"))
    )
    (net (code "58") (name "SWDIO") (class "Default")
      (node (ref "J2") (pin "2") (pinfunction "SWDIO_2") (pintype "bidirectional"))
      (node (ref "U2") (pin "16") (pinfunction "SWDIO_16") (pintype "bidirectional"))
    )
    (net (code "59") (name "VBUS") (class "Default")
      (node (ref "C9") (pin "P$1") (pinfunction "1_P$1") (pintype "bidirectional"))
      (node (ref "J3") (pin "P$1") (pinfunction "+5V_P$1") (pintype "bidirectional"))
      (node (ref "R18") (pin "1") (pinfunction "1_1") (pintype "passive"))
      (node (ref "U1") (pin "2") (pinfunction "EN_2") (pintype "bidirectional"))
      (node (ref "U1") (pin "3") (pinfunction "VIN_3") (pintype "bidirectional"))
      (node (ref "U1") (pin "4") (pinfunction "VIN_4") (pintype "bidirectional"))
      (node (ref "U4") (pin "P$6") (pinfunction "VUSB_P$6") (pintype "bidirectional"))
    )
    (net (code "60") (name "VCC") (class "Default")
      (node (ref "C10") (pin "P$1") (pinfunction "1_P$1") (pintype "bidirectional"))
      (node (ref "C11") (pin "P$1") (pinfunction "1_P$1") (pintype "bidirectional"))
      (node (ref "C3") (pin "1") (pinfunction "1_1") (pintype "bidirectional"))
      (node (ref "C4") (pin "1") (pinfunction "1_1") (pintype "bidirectional"))
      (node (ref "C5") (pin "1") (pinfunction "1_1") (pintype "bidirectional"))
      (node (ref "C6") (pin "1") (pinfunction "1_1") (pintype "bidirectional"))
      (node (ref "C7") (pin "1") (pinfunction "1_1") (pintype "bidirectional"))
      (node (ref "C8") (pin "1") (pinfunction "1_1") (pintype "bidirectional"))
      (node (ref "D10") (pin "A") (pinfunction "ANODE_A") (pintype "bidirectional"))
      (node (ref "D11") (pin "A") (pinfunction "ANODE_A") (pintype "bidirectional"))
      (node (ref "D12") (pin "A") (pinfunction "ANODE_A") (pintype "bidirectional"))
      (node (ref "D3") (pin "B2") (pinfunction "VCC_B2") (pintype "bidirectional"))
      (node (ref "D4") (pin "A") (pinfunction "ANODE_A") (pintype "bidirectional"))
      (node (ref "D5") (pin "A") (pinfunction "ANODE_A") (pintype "bidirectional"))
      (node (ref "D6") (pin "A") (pinfunction "ANODE_A") (pintype "bidirectional"))
      (node (ref "D7") (pin "A") (pinfunction "ANODE_A") (pintype "bidirectional"))
      (node (ref "D8") (pin "A") (pinfunction "ANODE_A") (pintype "bidirectional"))
      (node (ref "D9") (pin "A") (pinfunction "ANODE_A") (pintype "bidirectional"))
      (node (ref "J1") (pin "4") (pinfunction "VCC_4") (pintype "bidirectional"))
      (node (ref "J2") (pin "1") (pinfunction "VCC_1") (pintype "bidirectional"))
      (node (ref "R12") (pin "2") (pinfunction "2_2") (pintype "passive"))
      (node (ref "R13") (pin "1") (pinfunction "1_1") (pintype "passive"))
      (node (ref "R15") (pin "2") (pinfunction "2_2") (pintype "passive"))
      (node (ref "R16") (pin "2") (pinfunction "2_2") (pintype "passive"))
      (node (ref "S2") (pin "1") (pinfunction "P$1_1") (pintype "passive"))
      (node (ref "U1") (pin "5") (pinfunction "VOUT_5") (pintype "bidirectional"))
      (node (ref "U1") (pin "6") (pinfunction "VOUT_6") (pintype "bidirectional"))
      (node (ref "U1") (pin "7") (pinfunction "VOUT_7") (pintype "bidirectional"))
      (node (ref "U2") (pin "9") (pinfunction "VDD_9") (pintype "power_in"))
      (node (ref "U2") (pin "F4") (pinfunction "VDDH_F4") (pintype "power_in"))
      (node (ref "U3") (pin "6") (pinfunction "VDD_6") (pintype "bidirectional"))
      (node (ref "U3") (pin "7") (pinfunction "VREGIN_7") (pintype "bidirectional"))
      (node (ref "U5") (pin "2") (pinfunction "3V3_2") (pintype "bidirectional"))
      (node (ref "U6") (pin "2") (pinfunction "3V3_2") (pintype "bidirectional"))
    )
    (net (code "61") (name "unconnected-(D3-DAT2-PadD2)") (class "Default")
      (node (ref "D3") (pin "D2") (pinfunction "DAT2_D2") (pintype "bidirectional"))
    )
    (net (code "62") (name "unconnected-(D3-SD_DAT2-PadD3)") (class "Default")
      (node (ref "D3") (pin "D3") (pinfunction "SD_DAT2_D3") (pintype "bidirectional"))
    )
    (net (code "63") (name "unconnected-(J2-SWO-Pad6)") (class "Default")
      (node (ref "J2") (pin "6") (pinfunction "SWO_6") (pintype "bidirectional"))
    )
    (net (code "64") (name "unconnected-(U2-D+-PadE4)") (class "Default")
      (node (ref "U2") (pin "E4") (pinfunction "D+_E4") (pintype "bidirectional"))
    )
    (net (code "65") (name "unconnected-(U2-D--PadE5)") (class "Default")
      (node (ref "U2") (pin "E5") (pinfunction "D-_E5") (pintype "bidirectional"))
    )
    (net (code "66") (name "unconnected-(U2-P0.02{slash}AIN0-Pad5)") (class "Default")
      (node (ref "U2") (pin "5") (pinfunction "P0.02/AIN0_5") (pintype "bidirectional"))
    )
    (net (code "67") (name "unconnected-(U2-P0.03{slash}AIN1-Pad6)") (class "Default")
      (node (ref "U2") (pin "6") (pinfunction "P0.03/AIN1_6") (pintype "bidirectional"))
    )
    (net (code "68") (name "unconnected-(U2-P0.04{slash}AIN2-PadA3)") (class "Default")
      (node (ref "U2") (pin "A3") (pinfunction "P0.04/AIN2_A3") (pintype "bidirectional"))
    )
    (net (code "69") (name "unconnected-(U2-P0.05{slash}AIN3-PadA4)") (class "Default")
      (node (ref "U2") (pin "A4") (pinfunction "P0.05/AIN3_A4") (pintype "bidirectional"))
    )
    (net (code "70") (name "unconnected-(U2-P0.06-PadB4)") (class "Default")
      (node (ref "U2") (pin "B4") (pinfunction "P0.06_B4") (pintype "bidirectional"))
    )
    (net (code "71") (name "unconnected-(U2-P0.07-PadA5)") (class "Default")
      (node (ref "U2") (pin "A5") (pinfunction "P0.07_A5") (pintype "bidirectional"))
    )
    (net (code "72") (name "unconnected-(U2-P0.08-PadB5)") (class "Default")
      (node (ref "U2") (pin "B5") (pinfunction "P0.08_B5") (pintype "bidirectional"))
    )
    (net (code "73") (name "unconnected-(U2-P0.09{slash}NFC1-Pad7)") (class "Default")
      (node (ref "U2") (pin "7") (pinfunction "P0.09/NFC1_7") (pintype "bidirectional"))
    )
    (net (code "74") (name "unconnected-(U2-P0.10{slash}NFC2-Pad8)") (class "Default")
      (node (ref "U2") (pin "8") (pinfunction "P0.10/NFC2_8") (pintype "bidirectional"))
    )
    (net (code "75") (name "unconnected-(U2-P0.11-Pad11)") (class "Default")
      (node (ref "U2") (pin "11") (pinfunction "P0.11_11") (pintype "bidirectional"))
    )
    (net (code "76") (name "unconnected-(U2-P0.12-PadE6)") (class "Default")
      (node (ref "U2") (pin "E6") (pinfunction "P0.12_E6") (pintype "bidirectional"))
    )
    (net (code "77") (name "unconnected-(U2-P0.16-PadD3)") (class "Default")
      (node (ref "U2") (pin "D3") (pinfunction "P0.16_D3") (pintype "bidirectional"))
    )
    (net (code "78") (name "unconnected-(U2-P0.17-PadC3)") (class "Default")
      (node (ref "U2") (pin "C3") (pinfunction "P0.17_C3") (pintype "bidirectional"))
    )
    (net (code "79") (name "unconnected-(U2-P0.23-PadD1)") (class "Default")
      (node (ref "U2") (pin "D1") (pinfunction "P0.23_D1") (pintype "bidirectional"))
    )
    (net (code "80") (name "unconnected-(U2-P0.24-PadC1)") (class "Default")
      (node (ref "U2") (pin "C1") (pinfunction "P0.24_C1") (pintype "bidirectional"))
    )
    (net (code "81") (name "unconnected-(U2-P0.25-PadB1)") (class "Default")
      (node (ref "U2") (pin "B1") (pinfunction "P0.25_B1") (pintype "bidirectional"))
    )
    (net (code "82") (name "unconnected-(U2-P0.26{slash}SDA-Pad1)") (class "Default")
      (node (ref "U2") (pin "1") (pinfunction "P0.26/SDA_1") (pintype "bidirectional"))
    )
    (net (code "83") (name "unconnected-(U2-P0.27{slash}SCL-Pad2)") (class "Default")
      (node (ref "U2") (pin "2") (pinfunction "P0.27/SCL_2") (pintype "bidirectional"))
    )
    (net (code "84") (name "unconnected-(U2-P0.28{slash}AIN4-PadA1)") (class "Default")
      (node (ref "U2") (pin "A1") (pinfunction "P0.28/AIN4_A1") (pintype "bidirectional"))
    )
    (net (code "85") (name "unconnected-(U2-P0.29{slash}AIN5-PadA2)") (class "Default")
      (node (ref "U2") (pin "A2") (pinfunction "P0.29/AIN5_A2") (pintype "bidirectional"))
    )
    (net (code "86") (name "unconnected-(U2-P0.30{slash}AIN6-PadB2)") (class "Default")
      (node (ref "U2") (pin "B2") (pinfunction "P0.30/AIN6_B2") (pintype "bidirectional"))
    )
    (net (code "87") (name "unconnected-(U2-P0.31{slash}AIN7-PadB3)") (class "Default")
      (node (ref "U2") (pin "B3") (pinfunction "P0.31/AIN7_B3") (pintype "bidirectional"))
    )
    (net (code "88") (name "unconnected-(U2-P1.00-Pad12)") (class "Default")
      (node (ref "U2") (pin "12") (pinfunction "P1.00_12") (pintype "bidirectional"))
    )
    (net (code "89") (name "unconnected-(U2-P1.01-PadD5)") (class "Default")
      (node (ref "U2") (pin "D5") (pinfunction "P1.01_D5") (pintype "bidirectional"))
    )
    (net (code "90") (name "unconnected-(U2-P1.02-PadC5)") (class "Default")
      (node (ref "U2") (pin "C5") (pinfunction "P1.02_C5") (pintype "bidirectional"))
    )
    (net (code "91") (name "unconnected-(U2-P1.03-PadB6)") (class "Default")
      (node (ref "U2") (pin "B6") (pinfunction "P1.03_B6") (pintype "bidirectional"))
    )
    (net (code "92") (name "unconnected-(U2-P1.04-PadC6)") (class "Default")
      (node (ref "U2") (pin "C6") (pinfunction "P1.04_C6") (pintype "bidirectional"))
    )
    (net (code "93") (name "unconnected-(U2-P1.05-PadD6)") (class "Default")
      (node (ref "U2") (pin "D6") (pinfunction "P1.05_D6") (pintype "bidirectional"))
    )
    (net (code "94") (name "unconnected-(U2-P1.06-PadZ6)") (class "Default")
      (node (ref "U2") (pin "Z6") (pinfunction "P1.06_Z6") (pintype "bidirectional"))
    )
    (net (code "95") (name "unconnected-(U2-P1.07-PadE0)") (class "Default")
      (node (ref "U2") (pin "E0") (pinfunction "P1.07_E0") (pintype "bidirectional"))
    )
    (net (code "96") (name "unconnected-(U2-P1.08-PadA6)") (class "Default")
      (node (ref "U2") (pin "A6") (pinfunction "P1.08_A6") (pintype "bidirectional"))
    )
    (net (code "97") (name "unconnected-(U2-P1.09-PadE3)") (class "Default")
      (node (ref "U2") (pin "E3") (pinfunction "P1.09_E3") (pintype "bidirectional"))
    )
    (net (code "98") (name "unconnected-(U2-P1.10-PadZ5)") (class "Default")
      (node (ref "U2") (pin "Z5") (pinfunction "P1.10_Z5") (pintype "bidirectional"))
    )
    (net (code "99") (name "unconnected-(U2-P1.11-PadZ0)") (class "Default")
      (node (ref "U2") (pin "Z0") (pinfunction "P1.11_Z0") (pintype "bidirectional"))
    )
    (net (code "100") (name "unconnected-(U2-P1.12-PadZ1)") (class "Default")
      (node (ref "U2") (pin "Z1") (pinfunction "P1.12_Z1") (pintype "bidirectional"))
    )
    (net (code "101") (name "unconnected-(U2-P1.13-PadZ2)") (class "Default")
      (node (ref "U2") (pin "Z2") (pinfunction "P1.13_Z2") (pintype "bidirectional"))
    )
    (net (code "102") (name "unconnected-(U2-P1.14-PadZ3)") (class "Default")
      (node (ref "U2") (pin "Z3") (pinfunction "P1.14_Z3") (pintype "bidirectional"))
    )
    (net (code "103") (name "unconnected-(U2-P1.15-PadZ4)") (class "Default")
      (node (ref "U2") (pin "Z4") (pinfunction "P1.15_Z4") (pintype "bidirectional"))
    )
    (net (code "104") (name "unconnected-(U2-VBUS-PadF6)") (class "Default")
      (node (ref "U2") (pin "F6") (pinfunction "VBUS_F6") (pintype "power_in"))
    )
    (net (code "105") (name "unconnected-(U3-CTS-Pad15)") (class "Default")
      (node (ref "U3") (pin "15") (pinfunction "CTS_15") (pintype "bidirectional"))
    )
    (net (code "106") (name "unconnected-(U3-GPIO0{slash}CLK-Pad2)") (class "Default")
      (node (ref "U3") (pin "2") (pinfunction "GPIO0/CLK_2") (pintype "bidirectional"))
    )
    (net (code "107") (name "unconnected-(U3-GPIO1{slash}485-Pad1)") (class "Default")
      (node (ref "U3") (pin "1") (pinfunction "GPIO1/485_1") (pintype "bidirectional"))
    )
    (net (code "108") (name "unconnected-(U3-GPIO2{slash}TXT-Pad20)") (class "Default")
      (node (ref "U3") (pin "20") (pinfunction "GPIO2/TXT_20") (pintype "bidirectional"))
    )
    (net (code "109") (name "unconnected-(U3-GPIO3{slash}RXT-Pad19)") (class "Default")
      (node (ref "U3") (pin "19") (pinfunction "GPIO3/RXT_19") (pintype "bidirectional"))
    )
    (net (code "110") (name "unconnected-(U3-RTS-Pad16)") (class "Default")
      (node (ref "U3") (pin "16") (pinfunction "RTS_16") (pintype "bidirectional"))
    )
    (net (code "111") (name "unconnected-(U3-SUSPEND-Pad14)") (class "Default")
      (node (ref "U3") (pin "14") (pinfunction "SUSPEND_14") (pintype "bidirectional"))
    )
    (net (code "112") (name "unconnected-(U3-WAKEUP-Pad13)") (class "Default")
      (node (ref "U3") (pin "13") (pinfunction "WAKEUP_13") (pintype "bidirectional"))
    )
    (net (code "113") (name "unconnected-(U3-~{SUSPEND}-Pad11)") (class "Default")
      (node (ref "U3") (pin "11") (pinfunction "~{SUSPEND}_11") (pintype "bidirectional"))
    )
    (net (code "114") (name "unconnected-(U5-IO33-Pad9)") (class "Default")
      (node (ref "U5") (pin "9") (pinfunction "IO33_9") (pintype "bidirectional"))
    )
    (net (code "115") (name "unconnected-(U5-SENSOR_VN-Pad5)") (class "Default")
      (node (ref "U5") (pin "5") (pinfunction "SENSOR_VN_5") (pintype "bidirectional"))
    )
    (net (code "116") (name "unconnected-(U5-SENSOR_VP-Pad4)") (class "Default")
      (node (ref "U5") (pin "4") (pinfunction "SENSOR_VP_4") (pintype "bidirectional"))
    )
    (net (code "117") (name "unconnected-(U6-IO33-Pad9)") (class "Default")
      (node (ref "U6") (pin "9") (pinfunction "IO33_9") (pintype "bidirectional"))
    )
    (net (code "118") (name "unconnected-(U6-SENSOR_VN-Pad5)") (class "Default")
      (node (ref "U6") (pin "5") (pinfunction "SENSOR_VN_5") (pintype "bidirectional"))
    )
    (net (code "119") (name "unconnected-(U6-SENSOR_VP-Pad4)") (class "Default")
      (node (ref "U6") (pin "4") (pinfunction "SENSOR_VP_4") (pintype "bidirectional"))
    )
    (net (code "120") (name "~{NRF_RESET}") (class "Default")
      (node (ref "J2") (pin "3") (pinfunction "~{RESET}_3") (pintype "bidirectional"))
      (node (ref "U2") (pin "14") (pinfunction "P0.18/RESET_14") (pintype "bidirectional"))
      (node (ref "U5") (pin "36") (pinfunction "IO22_36") (pintype "bidirectional"))
      (node (ref "U6") (pin "36") (pinfunction "IO22_36") (pintype "bidirectional"))
    )
    (net (code "121") (name "~{SD_INSERTED}") (class "Default")
      (node (ref "D1") (pin "P$1") (pinfunction "CATHODE_P$1") (pintype "bidirectional"))
      (node (ref "J1") (pin "SW-B") (pinfunction "B_SW-B") (pintype "bidirectional"))
      (node (ref "R13") (pin "2") (pinfunction "2_2") (pintype "passive"))
      (node (ref "U5") (pin "12") (pinfunction "IO27_12") (pintype "bidirectional"))
      (node (ref "U6") (pin "12") (pinfunction "IO27_12") (pintype "bidirectional"))
    )
  )
)
